# Stereo_mixer_v3.net
KiCad netlist of a schematic drawn in EAGLE
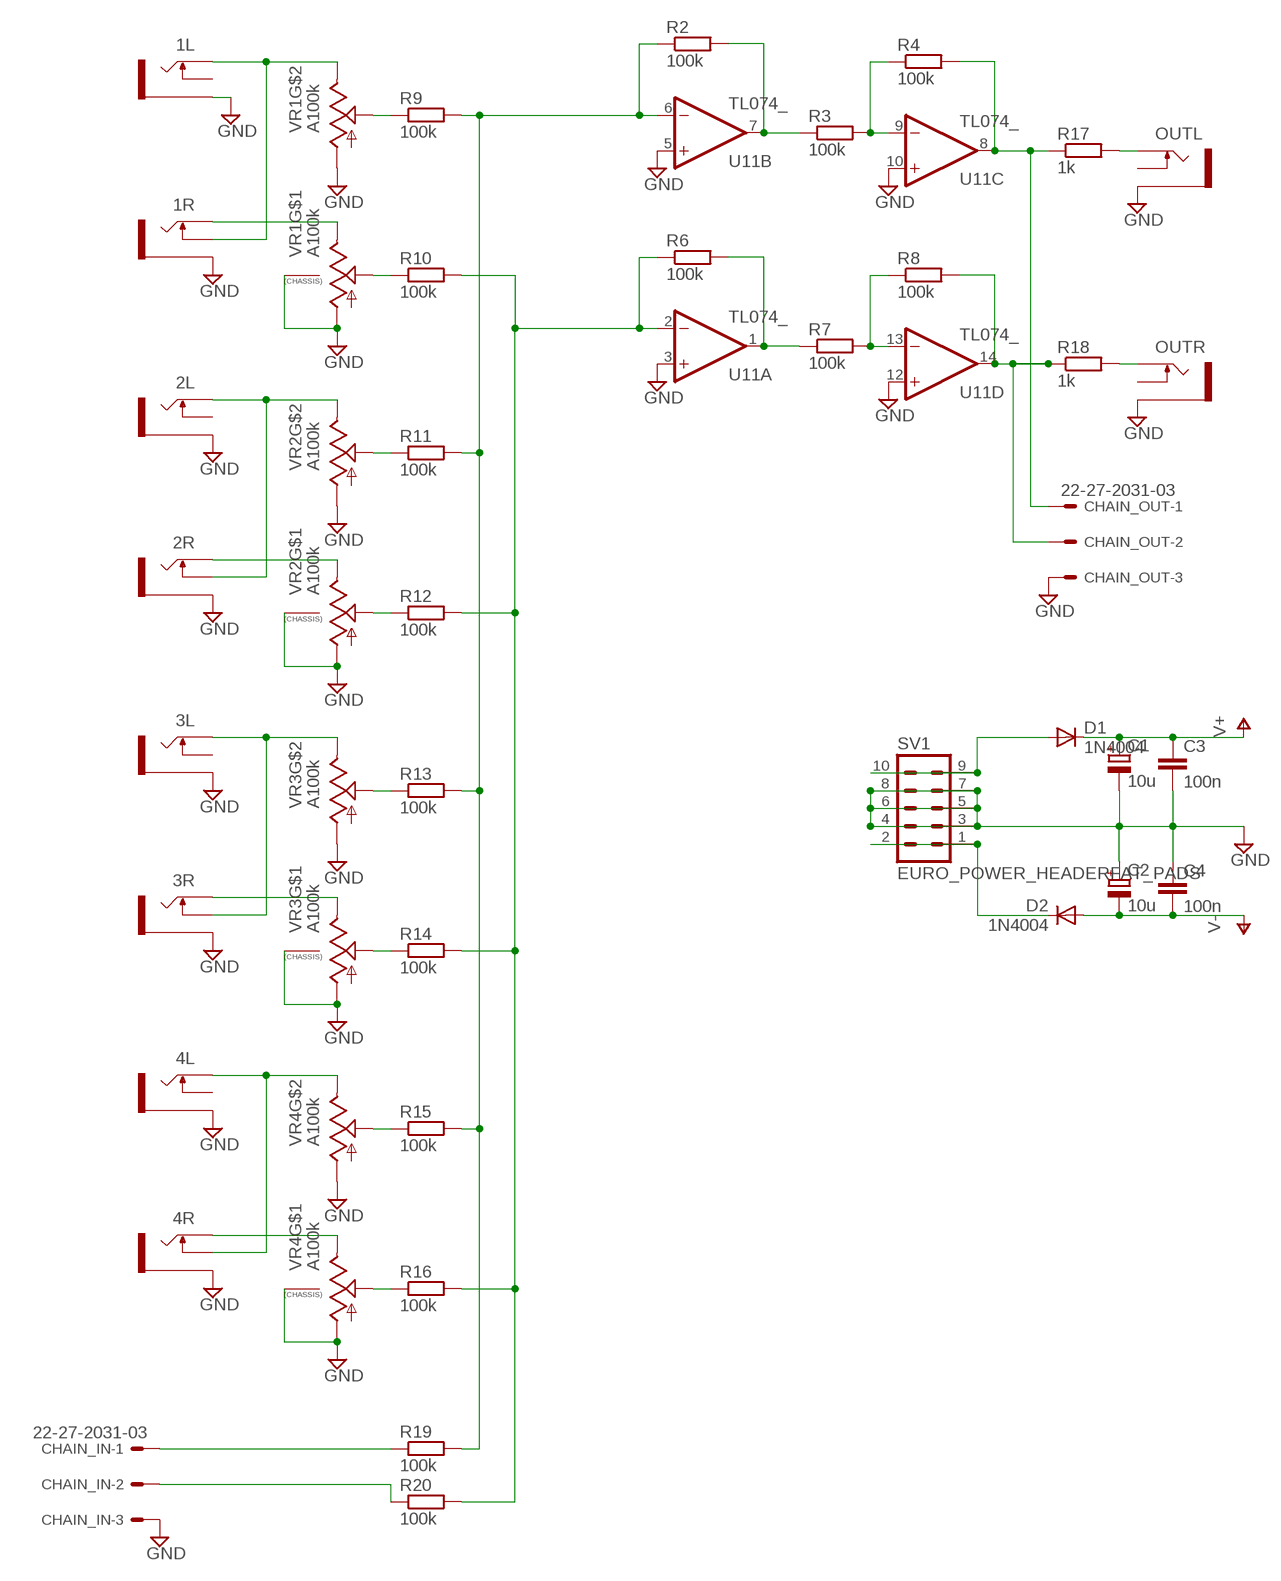
[diagram p0: schematic, sheet 1]

(export (version "E")
  (design (tool "Eeschema 10.0.6"))
  (components
    (comp (ref "1L")
      (value "THONKICONNNEW")
      (footprint "eagle-import:WQP-PJ301M-12_JACK")
      (libsource (lib "eagle-import") (part "THONKICONNNEW"))
    )
    (comp (ref "1R")
      (value "THONKICONNNEW")
      (footprint "eagle-import:WQP-PJ301M-12_JACK")
      (libsource (lib "eagle-import") (part "THONKICONNNEW"))
    )
    (comp (ref "2L")
      (value "THONKICONNNEW")
      (footprint "eagle-import:WQP-PJ301M-12_JACK")
      (libsource (lib "eagle-import") (part "THONKICONNNEW"))
    )
    (comp (ref "2R")
      (value "THONKICONNNEW")
      (footprint "eagle-import:WQP-PJ301M-12_JACK")
      (libsource (lib "eagle-import") (part "THONKICONNNEW"))
    )
    (comp (ref "3L")
      (value "THONKICONNNEW")
      (footprint "eagle-import:WQP-PJ301M-12_JACK")
      (libsource (lib "eagle-import") (part "THONKICONNNEW"))
    )
    (comp (ref "3R")
      (value "THONKICONNNEW")
      (footprint "eagle-import:WQP-PJ301M-12_JACK")
      (libsource (lib "eagle-import") (part "THONKICONNNEW"))
    )
    (comp (ref "4L")
      (value "THONKICONNNEW")
      (footprint "eagle-import:WQP-PJ301M-12_JACK")
      (libsource (lib "eagle-import") (part "THONKICONNNEW"))
    )
    (comp (ref "4R")
      (value "THONKICONNNEW")
      (footprint "eagle-import:WQP-PJ301M-12_JACK")
      (libsource (lib "eagle-import") (part "THONKICONNNEW"))
    )
    (comp (ref "C1")
      (value "10u")
      (footprint "eagle-import:E2,5-6")
      (libsource (lib "eagle-import") (part "CPOL-EUE2.5-6"))
    )
    (comp (ref "C2")
      (value "10u")
      (footprint "eagle-import:E2,5-6")
      (libsource (lib "eagle-import") (part "CPOL-EUE2.5-6"))
    )
    (comp (ref "C3")
      (value "100n")
      (footprint "eagle-import:C025-024X044")
      (libsource (lib "eagle-import") (part "C-EU025-024X044"))
    )
    (comp (ref "C4")
      (value "100n")
      (footprint "eagle-import:C025-024X044")
      (libsource (lib "eagle-import") (part "C-EU025-024X044"))
    )
    (comp (ref "CHAIN_IN")
      (value "22-27-2031-03")
      (footprint "eagle-import:6410-03")
      (fields (field (name "MF") "MOLEX"))
      (libsource (lib "eagle-import") (part "22-?-0327-2031"))
    )
    (comp (ref "CHAIN_OUT")
      (value "22-27-2031-03")
      (footprint "eagle-import:6410-03")
      (fields (field (name "MF") "MOLEX"))
      (libsource (lib "eagle-import") (part "22-?-0327-2031"))
    )
    (comp (ref "D1")
      (value "1N4004")
      (footprint "eagle-import:DO41-10")
      (libsource (lib "eagle-import") (part "1N4004"))
    )
    (comp (ref "D2")
      (value "1N4004")
      (footprint "eagle-import:DO41-10")
      (libsource (lib "eagle-import") (part "1N4004"))
    )
    (comp (ref "OUTL")
      (value "THONKICONNNEW")
      (footprint "eagle-import:WQP-PJ301M-12_JACK")
      (libsource (lib "eagle-import") (part "THONKICONNNEW"))
    )
    (comp (ref "OUTR")
      (value "THONKICONNNEW")
      (footprint "eagle-import:WQP-PJ301M-12_JACK")
      (libsource (lib "eagle-import") (part "THONKICONNNEW"))
    )
    (comp (ref "R2")
      (value "100k")
      (footprint "eagle-import:0207_7")
      (libsource (lib "eagle-import") (part "R-EU_0207/7"))
    )
    (comp (ref "R3")
      (value "100k")
      (footprint "eagle-import:0207_7")
      (libsource (lib "eagle-import") (part "R-EU_0207/7"))
    )
    (comp (ref "R4")
      (value "100k")
      (footprint "eagle-import:0207_7")
      (libsource (lib "eagle-import") (part "R-EU_0207/7"))
    )
    (comp (ref "R6")
      (value "100k")
      (footprint "eagle-import:0207_7")
      (libsource (lib "eagle-import") (part "R-EU_0207/7"))
    )
    (comp (ref "R7")
      (value "100k")
      (footprint "eagle-import:0207_7")
      (libsource (lib "eagle-import") (part "R-EU_0207/7"))
    )
    (comp (ref "R8")
      (value "100k")
      (footprint "eagle-import:0207_7")
      (libsource (lib "eagle-import") (part "R-EU_0207/7"))
    )
    (comp (ref "R9")
      (value "100k")
      (footprint "eagle-import:0207_7")
      (libsource (lib "eagle-import") (part "R-EU_0207/7"))
    )
    (comp (ref "R10")
      (value "100k")
      (footprint "eagle-import:0207_7")
      (libsource (lib "eagle-import") (part "R-EU_0207/7"))
    )
    (comp (ref "R11")
      (value "100k")
      (footprint "eagle-import:0207_7")
      (libsource (lib "eagle-import") (part "R-EU_0207/7"))
    )
    (comp (ref "R12")
      (value "100k")
      (footprint "eagle-import:0207_7")
      (libsource (lib "eagle-import") (part "R-EU_0207/7"))
    )
    (comp (ref "R13")
      (value "100k")
      (footprint "eagle-import:0207_7")
      (libsource (lib "eagle-import") (part "R-EU_0207/7"))
    )
    (comp (ref "R14")
      (value "100k")
      (footprint "eagle-import:0207_7")
      (libsource (lib "eagle-import") (part "R-EU_0207/7"))
    )
    (comp (ref "R15")
      (value "100k")
      (footprint "eagle-import:0207_7")
      (libsource (lib "eagle-import") (part "R-EU_0207/7"))
    )
    (comp (ref "R16")
      (value "100k")
      (footprint "eagle-import:0207_7")
      (libsource (lib "eagle-import") (part "R-EU_0207/7"))
    )
    (comp (ref "R17")
      (value "1k")
      (footprint "eagle-import:0207_7")
      (libsource (lib "eagle-import") (part "R-EU_0207/7"))
    )
    (comp (ref "R18")
      (value "1k")
      (footprint "eagle-import:0207_7")
      (libsource (lib "eagle-import") (part "R-EU_0207/7"))
    )
    (comp (ref "R19")
      (value "100k")
      (footprint "eagle-import:0207_7")
      (libsource (lib "eagle-import") (part "R-EU_0207/7"))
    )
    (comp (ref "R20")
      (value "100k")
      (footprint "eagle-import:0207_7")
      (libsource (lib "eagle-import") (part "R-EU_0207/7"))
    )
    (comp (ref "SV1")
      (value "EURO_POWER_HEADERFAT_PADS")
      (footprint "eagle-import:EURO_PWR_HEADER_FAT")
      (libsource (lib "eagle-import") (part "EURO_POWER_HEADERFAT_PADS"))
    )
    (comp (ref "U11")
      (value "TL074_")
      (footprint "eagle-import:DIL14")
      (libsource (lib "eagle-import") (part "TL074_"))
    )
    (comp (ref "VR1")
      (value "A100k")
      (footprint "eagle-import:DUAL_9MM_SNAP-IN_POT")
      (libsource (lib "eagle-import") (part "ALPHA-9MM-DUALPOT"))
    )
    (comp (ref "VR2")
      (value "A100k")
      (footprint "eagle-import:DUAL_9MM_SNAP-IN_POT")
      (libsource (lib "eagle-import") (part "ALPHA-9MM-DUALPOT"))
    )
    (comp (ref "VR3")
      (value "A100k")
      (footprint "eagle-import:DUAL_9MM_SNAP-IN_POT")
      (libsource (lib "eagle-import") (part "ALPHA-9MM-DUALPOT"))
    )
    (comp (ref "VR4")
      (value "A100k")
      (footprint "eagle-import:DUAL_9MM_SNAP-IN_POT")
      (libsource (lib "eagle-import") (part "ALPHA-9MM-DUALPOT"))
    )
  )
  (nets
    (net (code "1") (name "GND") (class "Default")
      (node (ref "1L") (pin "P$3_SLEEVE") (pinfunction "SLEEVE_P$3_SLEEVE") (pintype "passive"))
      (node (ref "1R") (pin "P$3_SLEEVE") (pinfunction "SLEEVE_P$3_SLEEVE") (pintype "passive"))
      (node (ref "2L") (pin "P$3_SLEEVE") (pinfunction "SLEEVE_P$3_SLEEVE") (pintype "passive"))
      (node (ref "2R") (pin "P$3_SLEEVE") (pinfunction "SLEEVE_P$3_SLEEVE") (pintype "passive"))
      (node (ref "3L") (pin "P$3_SLEEVE") (pinfunction "SLEEVE_P$3_SLEEVE") (pintype "passive"))
      (node (ref "3R") (pin "P$3_SLEEVE") (pinfunction "SLEEVE_P$3_SLEEVE") (pintype "passive"))
      (node (ref "4L") (pin "P$3_SLEEVE") (pinfunction "SLEEVE_P$3_SLEEVE") (pintype "passive"))
      (node (ref "4R") (pin "P$3_SLEEVE") (pinfunction "SLEEVE_P$3_SLEEVE") (pintype "passive"))
      (node (ref "C1") (pin "-") (pinfunction "-_-") (pintype "passive"))
      (node (ref "C2") (pin "+") (pinfunction "+_+") (pintype "passive"))
      (node (ref "C3") (pin "2") (pinfunction "2_2") (pintype "passive"))
      (node (ref "C4") (pin "1") (pinfunction "1_1") (pintype "passive"))
      (node (ref "CHAIN_IN") (pin "3") (pinfunction "S_3") (pintype "passive"))
      (node (ref "CHAIN_OUT") (pin "3") (pinfunction "S_3") (pintype "passive"))
      (node (ref "OUTL") (pin "P$3_SLEEVE") (pinfunction "SLEEVE_P$3_SLEEVE") (pintype "passive"))
      (node (ref "OUTR") (pin "P$3_SLEEVE") (pinfunction "SLEEVE_P$3_SLEEVE") (pintype "passive"))
      (node (ref "SV1") (pin "3") (pinfunction "3_3") (pintype "passive"))
      (node (ref "SV1") (pin "4") (pinfunction "4_4") (pintype "passive"))
      (node (ref "SV1") (pin "5") (pinfunction "5_5") (pintype "passive"))
      (node (ref "SV1") (pin "6") (pinfunction "6_6") (pintype "passive"))
      (node (ref "SV1") (pin "7") (pinfunction "7_7") (pintype "passive"))
      (node (ref "SV1") (pin "8") (pinfunction "8_8") (pintype "passive"))
      (node (ref "U11") (pin "10") (pinfunction "+IN_10") (pintype "input"))
      (node (ref "U11") (pin "12") (pinfunction "+IN_12") (pintype "input"))
      (node (ref "U11") (pin "3") (pinfunction "+IN_3") (pintype "input"))
      (node (ref "U11") (pin "5") (pinfunction "+IN_5") (pintype "input"))
      (node (ref "VR1") (pin "1") (pinfunction "A_1") (pintype "passive"))
      (node (ref "VR1") (pin "1B") (pinfunction "A_1B") (pintype "passive"))
      (node (ref "VR1") (pin "CHASSIS1") (pinfunction "P$1_CHASSIS1") (pintype "passive"))
      (node (ref "VR1") (pin "CHASSIS2") (pinfunction "P$1_CHASSIS2") (pintype "passive"))
      (node (ref "VR2") (pin "1") (pinfunction "A_1") (pintype "passive"))
      (node (ref "VR2") (pin "1B") (pinfunction "A_1B") (pintype "passive"))
      (node (ref "VR2") (pin "CHASSIS1") (pinfunction "P$1_CHASSIS1") (pintype "passive"))
      (node (ref "VR2") (pin "CHASSIS2") (pinfunction "P$1_CHASSIS2") (pintype "passive"))
      (node (ref "VR3") (pin "1") (pinfunction "A_1") (pintype "passive"))
      (node (ref "VR3") (pin "1B") (pinfunction "A_1B") (pintype "passive"))
      (node (ref "VR3") (pin "CHASSIS1") (pinfunction "P$1_CHASSIS1") (pintype "passive"))
      (node (ref "VR3") (pin "CHASSIS2") (pinfunction "P$1_CHASSIS2") (pintype "passive"))
      (node (ref "VR4") (pin "1") (pinfunction "A_1") (pintype "passive"))
      (node (ref "VR4") (pin "1B") (pinfunction "A_1B") (pintype "passive"))
      (node (ref "VR4") (pin "CHASSIS1") (pinfunction "P$1_CHASSIS1") (pintype "passive"))
      (node (ref "VR4") (pin "CHASSIS2") (pinfunction "P$1_CHASSIS2") (pintype "passive"))
    )
    (net (code "2") (name "Net-(1L-TIP)") (class "Default")
      (node (ref "1L") (pin "P$1_TIP") (pinfunction "TIP_P$1_TIP") (pintype "passive"))
      (node (ref "1R") (pin "P$2_SWITCH") (pinfunction "SWITCH_P$2_SWITCH") (pintype "passive"))
      (node (ref "VR1") (pin "3B") (pinfunction "E_3B") (pintype "passive"))
    )
    (net (code "3") (name "Net-(1R-TIP)") (class "Default")
      (node (ref "1R") (pin "P$1_TIP") (pinfunction "TIP_P$1_TIP") (pintype "passive"))
      (node (ref "VR1") (pin "3") (pinfunction "E_3") (pintype "passive"))
    )
    (net (code "4") (name "Net-(2L-TIP)") (class "Default")
      (node (ref "2L") (pin "P$1_TIP") (pinfunction "TIP_P$1_TIP") (pintype "passive"))
      (node (ref "2R") (pin "P$2_SWITCH") (pinfunction "SWITCH_P$2_SWITCH") (pintype "passive"))
      (node (ref "VR2") (pin "3B") (pinfunction "E_3B") (pintype "passive"))
    )
    (net (code "5") (name "Net-(2R-TIP)") (class "Default")
      (node (ref "2R") (pin "P$1_TIP") (pinfunction "TIP_P$1_TIP") (pintype "passive"))
      (node (ref "VR2") (pin "3") (pinfunction "E_3") (pintype "passive"))
    )
    (net (code "6") (name "Net-(3L-TIP)") (class "Default")
      (node (ref "3L") (pin "P$1_TIP") (pinfunction "TIP_P$1_TIP") (pintype "passive"))
      (node (ref "3R") (pin "P$2_SWITCH") (pinfunction "SWITCH_P$2_SWITCH") (pintype "passive"))
      (node (ref "VR3") (pin "3B") (pinfunction "E_3B") (pintype "passive"))
    )
    (net (code "7") (name "Net-(3R-TIP)") (class "Default")
      (node (ref "3R") (pin "P$1_TIP") (pinfunction "TIP_P$1_TIP") (pintype "passive"))
      (node (ref "VR3") (pin "3") (pinfunction "E_3") (pintype "passive"))
    )
    (net (code "8") (name "Net-(4L-TIP)") (class "Default")
      (node (ref "4L") (pin "P$1_TIP") (pinfunction "TIP_P$1_TIP") (pintype "passive"))
      (node (ref "4R") (pin "P$2_SWITCH") (pinfunction "SWITCH_P$2_SWITCH") (pintype "passive"))
      (node (ref "VR4") (pin "3B") (pinfunction "E_3B") (pintype "passive"))
    )
    (net (code "9") (name "Net-(4R-TIP)") (class "Default")
      (node (ref "4R") (pin "P$1_TIP") (pinfunction "TIP_P$1_TIP") (pintype "passive"))
      (node (ref "VR4") (pin "3") (pinfunction "E_3") (pintype "passive"))
    )
    (net (code "10") (name "Net-(CHAIN_INA-S)") (class "Default")
      (node (ref "CHAIN_IN") (pin "1") (pinfunction "S_1") (pintype "passive"))
      (node (ref "R19") (pin "1") (pinfunction "1_1") (pintype "passive"))
    )
    (net (code "11") (name "Net-(CHAIN_INB-S)") (class "Default")
      (node (ref "CHAIN_IN") (pin "2") (pinfunction "S_2") (pintype "passive"))
      (node (ref "R20") (pin "1") (pinfunction "1_1") (pintype "passive"))
    )
    (net (code "12") (name "Net-(CHAIN_OUTA-S)") (class "Default")
      (node (ref "CHAIN_OUT") (pin "1") (pinfunction "S_1") (pintype "passive"))
      (node (ref "R17") (pin "1") (pinfunction "1_1") (pintype "passive"))
      (node (ref "R4") (pin "2") (pinfunction "2_2") (pintype "passive"))
      (node (ref "U11") (pin "8") (pinfunction "OUT_8") (pintype "output"))
    )
    (net (code "13") (name "Net-(CHAIN_OUTB-S)") (class "Default")
      (node (ref "CHAIN_OUT") (pin "2") (pinfunction "S_2") (pintype "passive"))
      (node (ref "R18") (pin "1") (pinfunction "1_1") (pintype "passive"))
      (node (ref "R8") (pin "2") (pinfunction "2_2") (pintype "passive"))
      (node (ref "U11") (pin "14") (pinfunction "OUT_14") (pintype "output"))
    )
    (net (code "14") (name "Net-(D1-PadA)") (class "Default")
      (node (ref "D1") (pin "A") (pinfunction "A_A") (pintype "passive"))
      (node (ref "SV1") (pin "10") (pinfunction "10_10") (pintype "passive"))
      (node (ref "SV1") (pin "9") (pinfunction "9_9") (pintype "passive"))
    )
    (net (code "15") (name "Net-(D2-PadC)") (class "Default")
      (node (ref "D2") (pin "C") (pinfunction "C_C") (pintype "passive"))
      (node (ref "SV1") (pin "1") (pinfunction "1_1") (pintype "passive"))
      (node (ref "SV1") (pin "2") (pinfunction "2_2") (pintype "passive"))
    )
    (net (code "16") (name "Net-(OUTL-TIP)") (class "Default")
      (node (ref "OUTL") (pin "P$1_TIP") (pinfunction "TIP_P$1_TIP") (pintype "passive"))
      (node (ref "R17") (pin "2") (pinfunction "2_2") (pintype "passive"))
    )
    (net (code "17") (name "Net-(OUTR-TIP)") (class "Default")
      (node (ref "OUTR") (pin "P$1_TIP") (pinfunction "TIP_P$1_TIP") (pintype "passive"))
      (node (ref "R18") (pin "2") (pinfunction "2_2") (pintype "passive"))
    )
    (net (code "18") (name "Net-(U11A--IN)") (class "Default")
      (node (ref "R10") (pin "2") (pinfunction "2_2") (pintype "passive"))
      (node (ref "R12") (pin "2") (pinfunction "2_2") (pintype "passive"))
      (node (ref "R14") (pin "2") (pinfunction "2_2") (pintype "passive"))
      (node (ref "R16") (pin "2") (pinfunction "2_2") (pintype "passive"))
      (node (ref "R20") (pin "2") (pinfunction "2_2") (pintype "passive"))
      (node (ref "R6") (pin "1") (pinfunction "1_1") (pintype "passive"))
      (node (ref "U11") (pin "2") (pinfunction "-IN_2") (pintype "input"))
    )
    (net (code "19") (name "Net-(U11A-OUT)") (class "Default")
      (node (ref "R6") (pin "2") (pinfunction "2_2") (pintype "passive"))
      (node (ref "R7") (pin "1") (pinfunction "1_1") (pintype "passive"))
      (node (ref "U11") (pin "1") (pinfunction "OUT_1") (pintype "output"))
    )
    (net (code "20") (name "Net-(U11B--IN)") (class "Default")
      (node (ref "R11") (pin "2") (pinfunction "2_2") (pintype "passive"))
      (node (ref "R13") (pin "2") (pinfunction "2_2") (pintype "passive"))
      (node (ref "R15") (pin "2") (pinfunction "2_2") (pintype "passive"))
      (node (ref "R19") (pin "2") (pinfunction "2_2") (pintype "passive"))
      (node (ref "R2") (pin "1") (pinfunction "1_1") (pintype "passive"))
      (node (ref "R9") (pin "2") (pinfunction "2_2") (pintype "passive"))
      (node (ref "U11") (pin "6") (pinfunction "-IN_6") (pintype "input"))
    )
    (net (code "21") (name "Net-(U11B-OUT)") (class "Default")
      (node (ref "R2") (pin "2") (pinfunction "2_2") (pintype "passive"))
      (node (ref "R3") (pin "1") (pinfunction "1_1") (pintype "passive"))
      (node (ref "U11") (pin "7") (pinfunction "OUT_7") (pintype "output"))
    )
    (net (code "22") (name "Net-(U11C--IN)") (class "Default")
      (node (ref "R3") (pin "2") (pinfunction "2_2") (pintype "passive"))
      (node (ref "R4") (pin "1") (pinfunction "1_1") (pintype "passive"))
      (node (ref "U11") (pin "9") (pinfunction "-IN_9") (pintype "input"))
    )
    (net (code "23") (name "Net-(U11D--IN)") (class "Default")
      (node (ref "R7") (pin "2") (pinfunction "2_2") (pintype "passive"))
      (node (ref "R8") (pin "1") (pinfunction "1_1") (pintype "passive"))
      (node (ref "U11") (pin "13") (pinfunction "-IN_13") (pintype "input"))
    )
    (net (code "24") (name "Net-(VR1A-S)") (class "Default")
      (node (ref "R10") (pin "1") (pinfunction "1_1") (pintype "passive"))
      (node (ref "VR1") (pin "2") (pinfunction "S_2") (pintype "passive"))
    )
    (net (code "25") (name "Net-(VR1B-S)") (class "Default")
      (node (ref "R9") (pin "1") (pinfunction "1_1") (pintype "passive"))
      (node (ref "VR1") (pin "2B") (pinfunction "S_2B") (pintype "passive"))
    )
    (net (code "26") (name "Net-(VR2A-S)") (class "Default")
      (node (ref "R12") (pin "1") (pinfunction "1_1") (pintype "passive"))
      (node (ref "VR2") (pin "2") (pinfunction "S_2") (pintype "passive"))
    )
    (net (code "27") (name "Net-(VR2B-S)") (class "Default")
      (node (ref "R11") (pin "1") (pinfunction "1_1") (pintype "passive"))
      (node (ref "VR2") (pin "2B") (pinfunction "S_2B") (pintype "passive"))
    )
    (net (code "28") (name "Net-(VR3A-S)") (class "Default")
      (node (ref "R14") (pin "1") (pinfunction "1_1") (pintype "passive"))
      (node (ref "VR3") (pin "2") (pinfunction "S_2") (pintype "passive"))
    )
    (net (code "29") (name "Net-(VR3B-S)") (class "Default")
      (node (ref "R13") (pin "1") (pinfunction "1_1") (pintype "passive"))
      (node (ref "VR3") (pin "2B") (pinfunction "S_2B") (pintype "passive"))
    )
    (net (code "30") (name "Net-(VR4A-S)") (class "Default")
      (node (ref "R16") (pin "1") (pinfunction "1_1") (pintype "passive"))
      (node (ref "VR4") (pin "2") (pinfunction "S_2") (pintype "passive"))
    )
    (net (code "31") (name "Net-(VR4B-S)") (class "Default")
      (node (ref "R15") (pin "1") (pinfunction "1_1") (pintype "passive"))
      (node (ref "VR4") (pin "2B") (pinfunction "S_2B") (pintype "passive"))
    )
    (net (code "32") (name "V+") (class "Default")
      (node (ref "C1") (pin "+") (pinfunction "+_+") (pintype "passive"))
      (node (ref "C3") (pin "1") (pinfunction "1_1") (pintype "passive"))
      (node (ref "D1") (pin "C") (pinfunction "C_C") (pintype "passive"))
    )
    (net (code "33") (name "V-") (class "Default")
      (node (ref "C2") (pin "-") (pinfunction "-_-") (pintype "passive"))
      (node (ref "C4") (pin "2") (pinfunction "2_2") (pintype "passive"))
      (node (ref "D2") (pin "A") (pinfunction "A_A") (pintype "passive"))
    )
    (net (code "34") (name "unconnected-(1L-SWITCH-PadP$2_SWITCH)") (class "Default")
      (node (ref "1L") (pin "P$2_SWITCH") (pinfunction "SWITCH_P$2_SWITCH") (pintype "passive"))
    )
    (net (code "35") (name "unconnected-(2L-SWITCH-PadP$2_SWITCH)") (class "Default")
      (node (ref "2L") (pin "P$2_SWITCH") (pinfunction "SWITCH_P$2_SWITCH") (pintype "passive"))
    )
    (net (code "36") (name "unconnected-(3L-SWITCH-PadP$2_SWITCH)") (class "Default")
      (node (ref "3L") (pin "P$2_SWITCH") (pinfunction "SWITCH_P$2_SWITCH") (pintype "passive"))
    )
    (net (code "37") (name "unconnected-(4L-SWITCH-PadP$2_SWITCH)") (class "Default")
      (node (ref "4L") (pin "P$2_SWITCH") (pinfunction "SWITCH_P$2_SWITCH") (pintype "passive"))
    )
    (net (code "38") (name "unconnected-(OUTL-SWITCH-PadP$2_SWITCH)") (class "Default")
      (node (ref "OUTL") (pin "P$2_SWITCH") (pinfunction "SWITCH_P$2_SWITCH") (pintype "passive"))
    )
    (net (code "39") (name "unconnected-(OUTR-SWITCH-PadP$2_SWITCH)") (class "Default")
      (node (ref "OUTR") (pin "P$2_SWITCH") (pinfunction "SWITCH_P$2_SWITCH") (pintype "passive"))
    )
  )
)
